# KLine_bottom_board.net
KiCad netlist of a schematic drawn in EAGLE
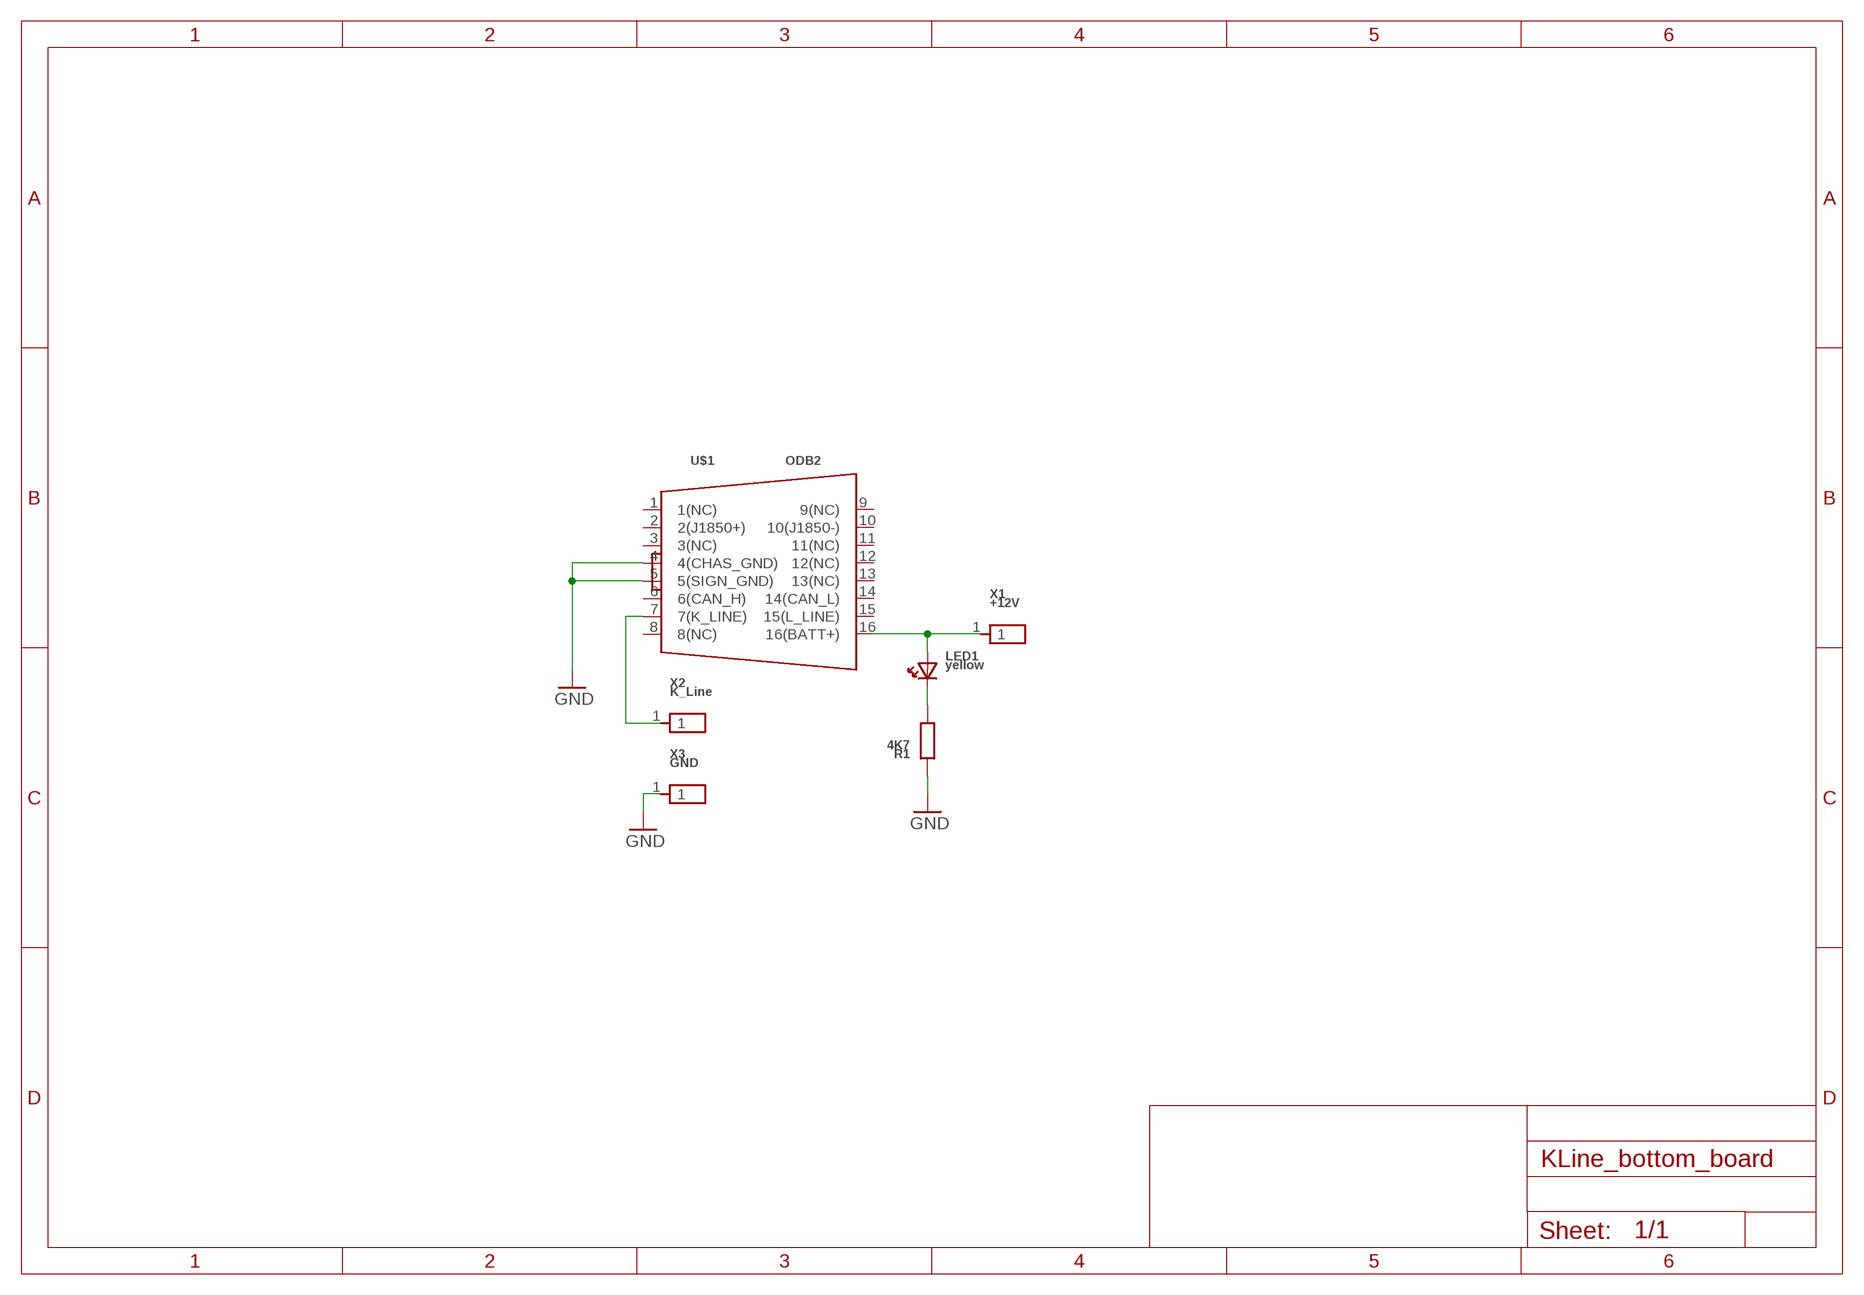
[diagram p0: schematic, sheet 1]

(export (version "E")
  (design (tool "Eeschema 10.0.6"))
  (components
    (comp (ref "LED1")
      (value "yellow")
      (footprint "eagle-import:LED_0805")
      (libsource (lib "eagle-import") (part "LED3MM(SMD0805)"))
    )
    (comp (ref "R1")
      (value "4K7")
      (footprint "eagle-import:RSMD_0805")
      (libsource (lib "eagle-import") (part "RSMD_0805"))
    )
    (comp (ref "U$1")
      (value "ODB2")
      (footprint "eagle-import:ODB2")
      (libsource (lib "eagle-import") (part "ODB2"))
    )
    (comp (ref "X1")
      (value "+12V")
      (footprint "eagle-import:PIN1X1_3.5MM_SIDE_BOARD")
      (libsource (lib "eagle-import") (part "PIN1X13.5MM_SIDE_BOARD"))
    )
    (comp (ref "X2")
      (value "K_Line")
      (footprint "eagle-import:PIN1X1_3.5MM_SIDE_BOARD")
      (libsource (lib "eagle-import") (part "PIN1X13.5MM_SIDE_BOARD"))
    )
    (comp (ref "X3")
      (value "GND")
      (footprint "eagle-import:PIN1X1_3.5MM_SIDE_BOARD")
      (libsource (lib "eagle-import") (part "PIN1X13.5MM_SIDE_BOARD"))
    )
  )
  (nets
    (net (code "1") (name "GND") (class "Default")
      (node (ref "R1") (pin "PAD_1") (pinfunction "PIN1_PAD_1") (pintype "passive"))
      (node (ref "U$1") (pin "4") (pinfunction "4(CHAS_GND)_4") (pintype "bidirectional"))
      (node (ref "U$1") (pin "5") (pinfunction "5(SIGN_GND)_5") (pintype "bidirectional"))
      (node (ref "X3") (pin "1") (pinfunction "1_1") (pintype "bidirectional"))
    )
    (net (code "2") (name "Net-(R1-PIN0)") (class "Default")
      (node (ref "LED1") (pin "CATHODE") (pinfunction "CATHODE_CATHODE") (pintype "passive"))
      (node (ref "R1") (pin "PAD_0") (pinfunction "PIN0_PAD_0") (pintype "passive"))
    )
    (net (code "3") (name "Net-(U$1-7(K_LINE))") (class "Default")
      (node (ref "U$1") (pin "7") (pinfunction "7(K_LINE)_7") (pintype "bidirectional"))
      (node (ref "X2") (pin "1") (pinfunction "1_1") (pintype "bidirectional"))
    )
    (net (code "4") (name "Net-(U$1-16(BATT+))") (class "Default")
      (node (ref "LED1") (pin "ANODE") (pinfunction "ANODE_ANODE") (pintype "passive"))
      (node (ref "U$1") (pin "16") (pinfunction "16(BATT+)_16") (pintype "bidirectional"))
      (node (ref "X1") (pin "1") (pinfunction "1_1") (pintype "bidirectional"))
    )
    (net (code "5") (name "unconnected-(U$1-1(NC)-Pad1)") (class "Default")
      (node (ref "U$1") (pin "1") (pinfunction "1(NC)_1") (pintype "bidirectional"))
    )
    (net (code "6") (name "unconnected-(U$1-2(J1850+)-Pad2)") (class "Default")
      (node (ref "U$1") (pin "2") (pinfunction "2(J1850+)_2") (pintype "bidirectional"))
    )
    (net (code "7") (name "unconnected-(U$1-3(NC)-Pad3)") (class "Default")
      (node (ref "U$1") (pin "3") (pinfunction "3(NC)_3") (pintype "bidirectional"))
    )
    (net (code "8") (name "unconnected-(U$1-6(CAN_H)-Pad6)") (class "Default")
      (node (ref "U$1") (pin "6") (pinfunction "6(CAN_H)_6") (pintype "bidirectional"))
    )
    (net (code "9") (name "unconnected-(U$1-8(NC)-Pad8)") (class "Default")
      (node (ref "U$1") (pin "8") (pinfunction "8(NC)_8") (pintype "bidirectional"))
    )
    (net (code "10") (name "unconnected-(U$1-9(NC)-Pad9)") (class "Default")
      (node (ref "U$1") (pin "9") (pinfunction "9(NC)_9") (pintype "bidirectional"))
    )
    (net (code "11") (name "unconnected-(U$1-10(J1850-)-Pad10)") (class "Default")
      (node (ref "U$1") (pin "10") (pinfunction "10(J1850-)_10") (pintype "bidirectional"))
    )
    (net (code "12") (name "unconnected-(U$1-11(NC)-Pad11)") (class "Default")
      (node (ref "U$1") (pin "11") (pinfunction "11(NC)_11") (pintype "bidirectional"))
    )
    (net (code "13") (name "unconnected-(U$1-12(NC)-Pad12)") (class "Default")
      (node (ref "U$1") (pin "12") (pinfunction "12(NC)_12") (pintype "bidirectional"))
    )
    (net (code "14") (name "unconnected-(U$1-13(NC)-Pad13)") (class "Default")
      (node (ref "U$1") (pin "13") (pinfunction "13(NC)_13") (pintype "bidirectional"))
    )
    (net (code "15") (name "unconnected-(U$1-14(CAN_L)-Pad14)") (class "Default")
      (node (ref "U$1") (pin "14") (pinfunction "14(CAN_L)_14") (pintype "bidirectional"))
    )
    (net (code "16") (name "unconnected-(U$1-15(L_LINE)-Pad15)") (class "Default")
      (node (ref "U$1") (pin "15") (pinfunction "15(L_LINE)_15") (pintype "bidirectional"))
    )
  )
)
